# Minisumo_edu.net
KiCad netlist of a schematic drawn in EAGLE
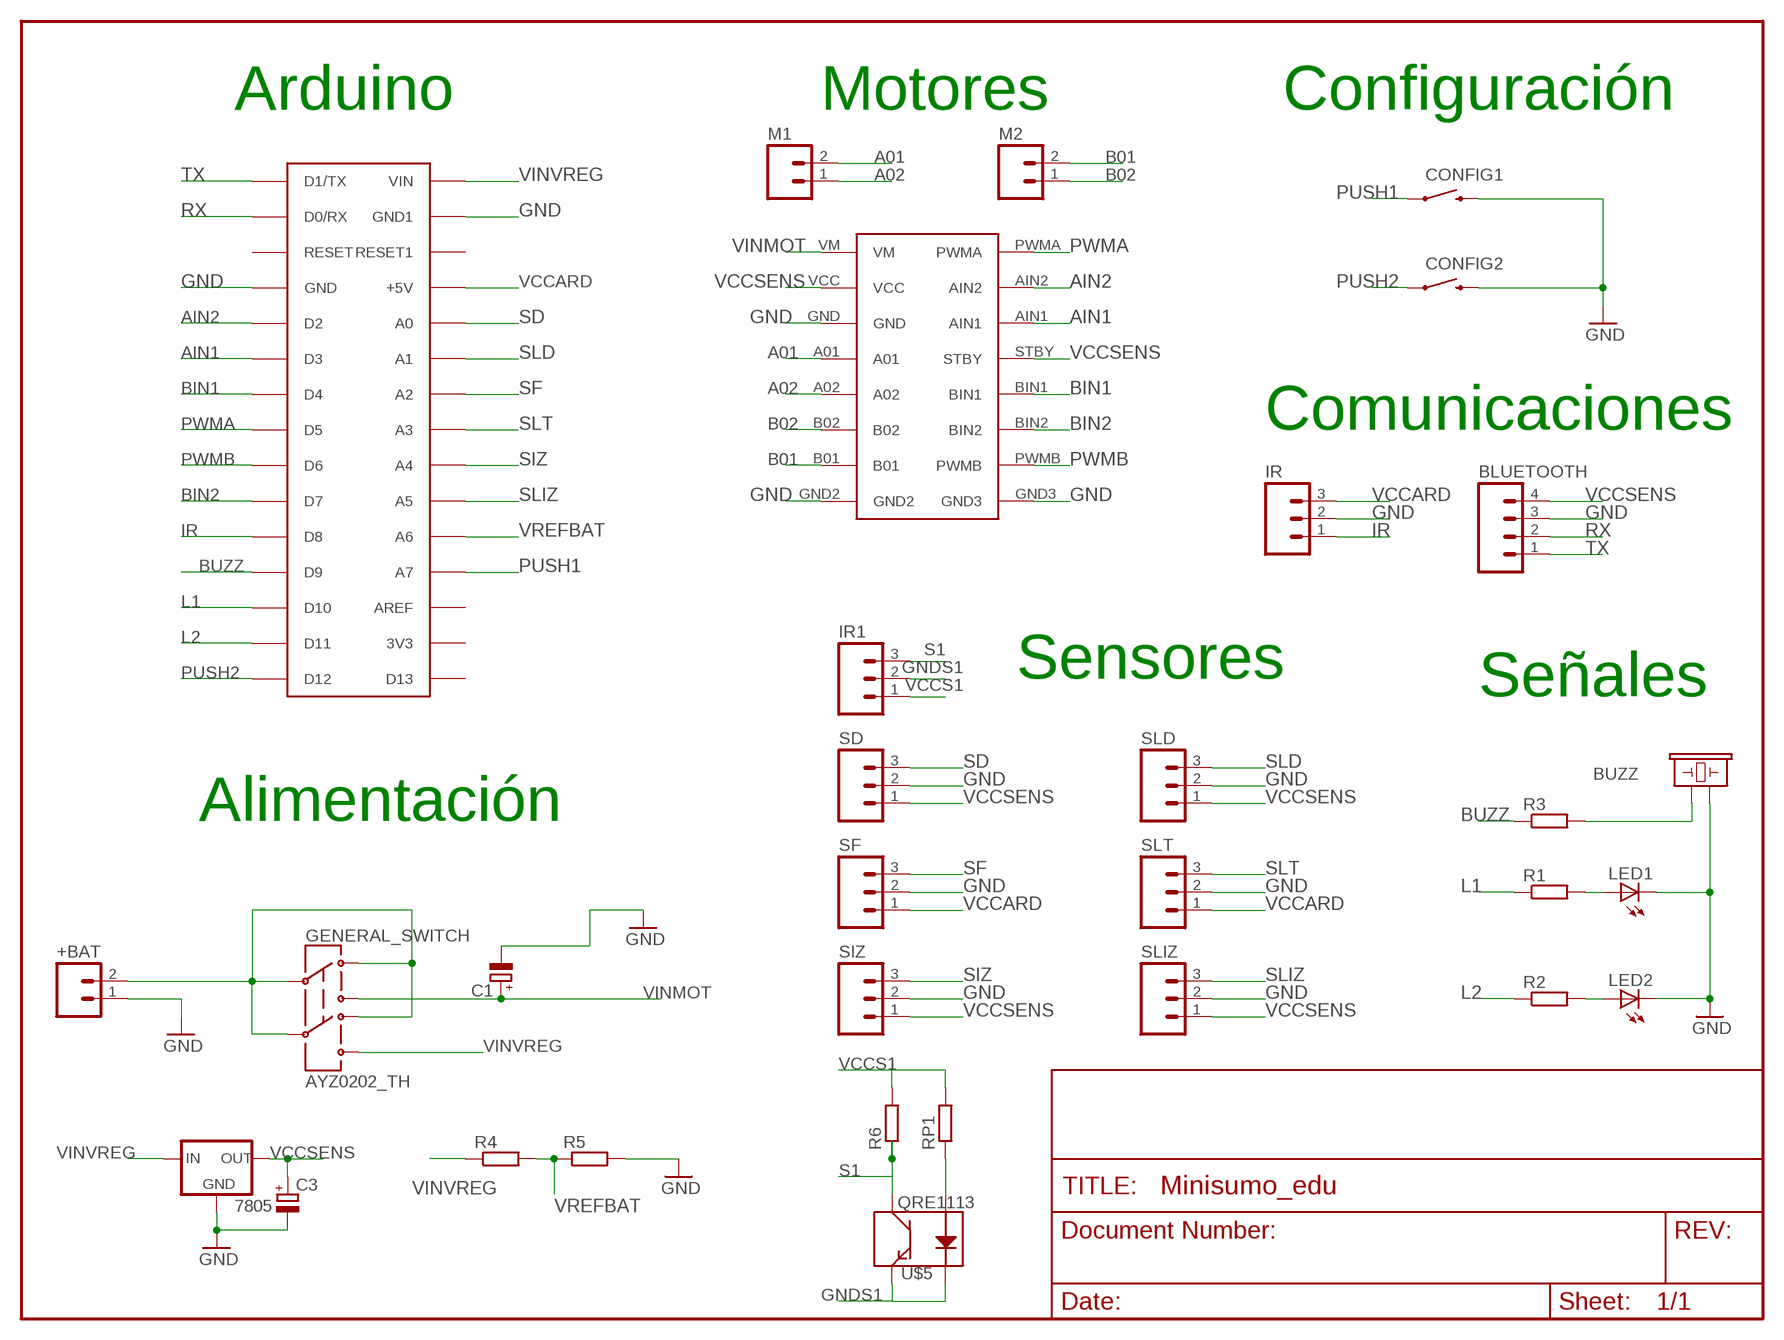
[diagram p0: schematic, sheet 1]

(export (version "E")
  (design (tool "Eeschema 10.0.6"))
  (components
    (comp (ref "+BAT")
      (value "M02LOCK_LONGPADS")
      (footprint "eagle-import:1X02_LOCK_LONGPADS")
      (libsource (lib "eagle-import") (part "M02LOCK_LONGPADS"))
    )
    (comp (ref "7805")
      (value "V_REG_78XXSINK")
      (footprint "eagle-import:TO220-IGO")
      (libsource (lib "eagle-import") (part "V_REG_78XXSINK"))
    )
    (comp (ref "BLUETOOTH")
      (value "M04LONGPADS")
      (footprint "eagle-import:1X04_LONGPADS")
      (libsource (lib "eagle-import") (part "M04LONGPADS"))
    )
    (comp (ref "BUZZ")
      (value "BUZZERPTH")
      (footprint "eagle-import:BUZZER-12MM")
      (libsource (lib "eagle-import") (part "BUZZERPTH"))
    )
    (comp (ref "C1")
      (value "CPOL-EUE2.5-6")
      (footprint "eagle-import:E2,5-6")
      (libsource (lib "eagle-import") (part "CPOL-EUE2.5-6"))
    )
    (comp (ref "C3")
      (value "CPOL-EUE2.5-6")
      (footprint "eagle-import:E2,5-6")
      (libsource (lib "eagle-import") (part "CPOL-EUE2.5-6"))
    )
    (comp (ref "CONFIG1")
      (value "SWITCH-MOMENTARY-2PTH")
      (footprint "eagle-import:TACTILE-PTH")
      (libsource (lib "eagle-import") (part "SWITCH-MOMENTARY-2PTH"))
    )
    (comp (ref "CONFIG2")
      (value "SWITCH-MOMENTARY-2PTH")
      (footprint "eagle-import:TACTILE-PTH")
      (libsource (lib "eagle-import") (part "SWITCH-MOMENTARY-2PTH"))
    )
    (comp (ref "GENERAL_SWITCH")
      (value "AYZ0202_TH")
      (footprint "eagle-import:AYZ0202_TH")
      (libsource (lib "eagle-import") (part "AYZ0202_TH"))
    )
    (comp (ref "IR")
      (value "M03LONGPADS")
      (footprint "eagle-import:1X03_LONGPADS")
      (libsource (lib "eagle-import") (part "M03LONGPADS"))
    )
    (comp (ref "IR1")
      (value "M03LONGPADS")
      (footprint "eagle-import:1X03_LONGPADS")
      (libsource (lib "eagle-import") (part "M03LONGPADS"))
    )
    (comp (ref "LED1")
      (value "LED3MM")
      (footprint "eagle-import:LED3MM")
      (libsource (lib "eagle-import") (part "LED3MM"))
    )
    (comp (ref "LED2")
      (value "LED3MM")
      (footprint "eagle-import:LED3MM")
      (libsource (lib "eagle-import") (part "LED3MM"))
    )
    (comp (ref "M1")
      (value "M02LOCK_LONGPADS")
      (footprint "eagle-import:1X02_LOCK_LONGPADS")
      (libsource (lib "eagle-import") (part "M02LOCK_LONGPADS"))
    )
    (comp (ref "M2")
      (value "M02LOCK_LONGPADS")
      (footprint "eagle-import:1X02_LOCK_LONGPADS")
      (libsource (lib "eagle-import") (part "M02LOCK_LONGPADS"))
    )
    (comp (ref "R1")
      (value "R-EU_0207/7")
      (footprint "eagle-import:0207_7")
      (libsource (lib "eagle-import") (part "R-EU_0207/7"))
    )
    (comp (ref "R2")
      (value "R-EU_0207/7")
      (footprint "eagle-import:0207_7")
      (libsource (lib "eagle-import") (part "R-EU_0207/7"))
    )
    (comp (ref "R3")
      (value "R-EU_0207/7")
      (footprint "eagle-import:0207_7")
      (libsource (lib "eagle-import") (part "R-EU_0207/7"))
    )
    (comp (ref "R4")
      (value "R-EU_0207/7")
      (footprint "eagle-import:0207_7")
      (libsource (lib "eagle-import") (part "R-EU_0207/7"))
    )
    (comp (ref "R5")
      (value "R-EU_0207/7")
      (footprint "eagle-import:0207_7")
      (libsource (lib "eagle-import") (part "R-EU_0207/7"))
    )
    (comp (ref "R6")
      (value "R-EU_M0805")
      (footprint "eagle-import:M0805@1")
      (libsource (lib "eagle-import") (part "resistor_R-EU_M0805"))
    )
    (comp (ref "RP1")
      (value "R-EU_M0805")
      (footprint "eagle-import:M0805")
      (libsource (lib "eagle-import") (part "R-EU_M0805"))
    )
    (comp (ref "SD")
      (value "M03LONGPADS")
      (footprint "eagle-import:1X03_LONGPADS")
      (libsource (lib "eagle-import") (part "M03LONGPADS"))
    )
    (comp (ref "SF")
      (value "M03LONGPADS")
      (footprint "eagle-import:1X03_LONGPADS")
      (libsource (lib "eagle-import") (part "M03LONGPADS"))
    )
    (comp (ref "SIZ")
      (value "M03LONGPADS")
      (footprint "eagle-import:1X03_LONGPADS")
      (libsource (lib "eagle-import") (part "M03LONGPADS"))
    )
    (comp (ref "SLD")
      (value "M03LONGPADS")
      (footprint "eagle-import:1X03_LONGPADS")
      (libsource (lib "eagle-import") (part "M03LONGPADS"))
    )
    (comp (ref "SLIZ")
      (value "M03LONGPADS")
      (footprint "eagle-import:1X03_LONGPADS")
      (libsource (lib "eagle-import") (part "M03LONGPADS"))
    )
    (comp (ref "SLT")
      (value "M03LONGPADS")
      (footprint "eagle-import:1X03_LONGPADS")
      (libsource (lib "eagle-import") (part "M03LONGPADS"))
    )
    (comp (ref "U$1")
      (value "ARDUINONANO")
      (footprint "eagle-import:PDIP-32")
      (libsource (lib "eagle-import") (part "ARDUINONANO"))
    )
    (comp (ref "U$3")
      (value "TB6612FNG_SPARKFUN")
      (footprint "eagle-import:TB6612FNG_SPARKFUN")
      (libsource (lib "eagle-import") (part "TB6612FNG_SPARKFUN"))
    )
    (comp (ref "U$5")
      (value "QRE1113")
      (footprint "eagle-import:QRE1113")
      (libsource (lib "eagle-import") (part "QRE1113"))
    )
  )
  (nets
    (net (code "1") (name "/A01") (class "Default")
      (node (ref "M1") (pin "2") (pinfunction "2_2") (pintype "passive"))
      (node (ref "U$3") (pin "A01") (pinfunction "A01_A01") (pintype "bidirectional"))
    )
    (net (code "2") (name "/A02") (class "Default")
      (node (ref "M1") (pin "1") (pinfunction "1_1") (pintype "passive"))
      (node (ref "U$3") (pin "A02") (pinfunction "A02_A02") (pintype "bidirectional"))
    )
    (net (code "3") (name "/AIN1") (class "Default")
      (node (ref "U$1") (pin "D3") (pinfunction "D3_D3") (pintype "bidirectional"))
      (node (ref "U$3") (pin "AIN1") (pinfunction "AIN1_AIN1") (pintype "bidirectional"))
    )
    (net (code "4") (name "/AIN2") (class "Default")
      (node (ref "U$1") (pin "D2") (pinfunction "D2_D2") (pintype "bidirectional"))
      (node (ref "U$3") (pin "AIN2") (pinfunction "AIN2_AIN2") (pintype "bidirectional"))
    )
    (net (code "5") (name "/B01") (class "Default")
      (node (ref "M2") (pin "2") (pinfunction "2_2") (pintype "passive"))
      (node (ref "U$3") (pin "B01") (pinfunction "B01_B01") (pintype "bidirectional"))
    )
    (net (code "6") (name "/B02") (class "Default")
      (node (ref "M2") (pin "1") (pinfunction "1_1") (pintype "passive"))
      (node (ref "U$3") (pin "B02") (pinfunction "B02_B02") (pintype "bidirectional"))
    )
    (net (code "7") (name "/BIN1") (class "Default")
      (node (ref "U$1") (pin "D4") (pinfunction "D4_D4") (pintype "bidirectional"))
      (node (ref "U$3") (pin "BIN1") (pinfunction "BIN1_BIN1") (pintype "bidirectional"))
    )
    (net (code "8") (name "/BIN2") (class "Default")
      (node (ref "U$1") (pin "D7") (pinfunction "D7_D7") (pintype "bidirectional"))
      (node (ref "U$3") (pin "BIN2") (pinfunction "BIN2_BIN2") (pintype "bidirectional"))
    )
    (net (code "9") (name "/BUZZ") (class "Default")
      (node (ref "R3") (pin "1") (pinfunction "1_1") (pintype "passive"))
      (node (ref "U$1") (pin "D9") (pinfunction "D9_D9") (pintype "bidirectional"))
    )
    (net (code "10") (name "/GNDS1") (class "Default")
      (node (ref "IR1") (pin "2") (pinfunction "2_2") (pintype "passive"))
      (node (ref "U$5") (pin "2") (pinfunction "K_2") (pintype "bidirectional"))
      (node (ref "U$5") (pin "4") (pinfunction "E_4") (pintype "bidirectional"))
    )
    (net (code "11") (name "/IR") (class "Default")
      (node (ref "IR") (pin "1") (pinfunction "1_1") (pintype "passive"))
      (node (ref "U$1") (pin "D8") (pinfunction "D8_D8") (pintype "bidirectional"))
    )
    (net (code "12") (name "/L1") (class "Default")
      (node (ref "R1") (pin "1") (pinfunction "1_1") (pintype "passive"))
      (node (ref "U$1") (pin "D10") (pinfunction "D10_D10") (pintype "bidirectional"))
    )
    (net (code "13") (name "/L2") (class "Default")
      (node (ref "R2") (pin "1") (pinfunction "1_1") (pintype "passive"))
      (node (ref "U$1") (pin "D11") (pinfunction "D11_D11") (pintype "bidirectional"))
    )
    (net (code "14") (name "/PUSH1") (class "Default")
      (node (ref "CONFIG1") (pin "1") (pinfunction "1_1") (pintype "passive"))
      (node (ref "U$1") (pin "A7") (pinfunction "A7_A7") (pintype "bidirectional"))
    )
    (net (code "15") (name "/PUSH2") (class "Default")
      (node (ref "CONFIG2") (pin "1") (pinfunction "1_1") (pintype "passive"))
      (node (ref "U$1") (pin "D12") (pinfunction "D12_D12") (pintype "bidirectional"))
    )
    (net (code "16") (name "/PWMA") (class "Default")
      (node (ref "U$1") (pin "D5") (pinfunction "D5_D5") (pintype "bidirectional"))
      (node (ref "U$3") (pin "PWMA") (pinfunction "PWMA_PWMA") (pintype "bidirectional"))
    )
    (net (code "17") (name "/PWMB") (class "Default")
      (node (ref "U$1") (pin "D6") (pinfunction "D6_D6") (pintype "bidirectional"))
      (node (ref "U$3") (pin "PWMB") (pinfunction "PWMB_PWMB") (pintype "bidirectional"))
    )
    (net (code "18") (name "/RX") (class "Default")
      (node (ref "BLUETOOTH") (pin "2") (pinfunction "2_2") (pintype "passive"))
      (node (ref "U$1") (pin "D0/RX") (pinfunction "D0/RX_D0/RX") (pintype "bidirectional"))
    )
    (net (code "19") (name "/S1") (class "Default")
      (node (ref "IR1") (pin "3") (pinfunction "3_3") (pintype "passive"))
      (node (ref "R6") (pin "1") (pinfunction "1_1") (pintype "passive"))
      (node (ref "U$5") (pin "3") (pinfunction "C_3") (pintype "bidirectional"))
    )
    (net (code "20") (name "/SD") (class "Default")
      (node (ref "SD") (pin "3") (pinfunction "3_3") (pintype "passive"))
      (node (ref "U$1") (pin "A0") (pinfunction "A0_A0") (pintype "bidirectional"))
    )
    (net (code "21") (name "/SF") (class "Default")
      (node (ref "SF") (pin "3") (pinfunction "3_3") (pintype "passive"))
      (node (ref "U$1") (pin "A2") (pinfunction "A2_A2") (pintype "bidirectional"))
    )
    (net (code "22") (name "/SIZ") (class "Default")
      (node (ref "SIZ") (pin "3") (pinfunction "3_3") (pintype "passive"))
      (node (ref "U$1") (pin "A4") (pinfunction "A4_A4") (pintype "bidirectional"))
    )
    (net (code "23") (name "/SLD") (class "Default")
      (node (ref "SLD") (pin "3") (pinfunction "3_3") (pintype "passive"))
      (node (ref "U$1") (pin "A1") (pinfunction "A1_A1") (pintype "bidirectional"))
    )
    (net (code "24") (name "/SLIZ") (class "Default")
      (node (ref "SLIZ") (pin "3") (pinfunction "3_3") (pintype "passive"))
      (node (ref "U$1") (pin "A5") (pinfunction "A5_A5") (pintype "bidirectional"))
    )
    (net (code "25") (name "/SLT") (class "Default")
      (node (ref "SLT") (pin "3") (pinfunction "3_3") (pintype "passive"))
      (node (ref "U$1") (pin "A3") (pinfunction "A3_A3") (pintype "bidirectional"))
    )
    (net (code "26") (name "/TX") (class "Default")
      (node (ref "BLUETOOTH") (pin "1") (pinfunction "1_1") (pintype "passive"))
      (node (ref "U$1") (pin "D1/TX") (pinfunction "D1/TX_D1/TX") (pintype "bidirectional"))
    )
    (net (code "27") (name "/VCCARD") (class "Default")
      (node (ref "IR") (pin "3") (pinfunction "3_3") (pintype "passive"))
      (node (ref "SF") (pin "1") (pinfunction "1_1") (pintype "passive"))
      (node (ref "SLT") (pin "1") (pinfunction "1_1") (pintype "passive"))
      (node (ref "U$1") (pin "+5V") (pinfunction "+5V_+5V") (pintype "bidirectional"))
    )
    (net (code "28") (name "/VCCS1") (class "Default")
      (node (ref "IR1") (pin "1") (pinfunction "1_1") (pintype "passive"))
      (node (ref "R6") (pin "2") (pinfunction "2_2") (pintype "passive"))
      (node (ref "RP1") (pin "2") (pinfunction "2_2") (pintype "passive"))
    )
    (net (code "29") (name "/VCCSENS") (class "Default")
      (node (ref "7805") (pin "OUT") (pinfunction "OUT_OUT") (pintype "output"))
      (node (ref "BLUETOOTH") (pin "4") (pinfunction "4_4") (pintype "passive"))
      (node (ref "C3") (pin "+") (pinfunction "+_+") (pintype "passive"))
      (node (ref "SD") (pin "1") (pinfunction "1_1") (pintype "passive"))
      (node (ref "SIZ") (pin "1") (pinfunction "1_1") (pintype "passive"))
      (node (ref "SLD") (pin "1") (pinfunction "1_1") (pintype "passive"))
      (node (ref "SLIZ") (pin "1") (pinfunction "1_1") (pintype "passive"))
      (node (ref "U$3") (pin "STBY") (pinfunction "STBY_STBY") (pintype "bidirectional"))
      (node (ref "U$3") (pin "VCC") (pinfunction "VCC_VCC") (pintype "bidirectional"))
    )
    (net (code "30") (name "/VINMOT") (class "Default")
      (node (ref "C1") (pin "+") (pinfunction "+_+") (pintype "passive"))
      (node (ref "GENERAL_SWITCH") (pin "B1") (pinfunction "B1_B1") (pintype "bidirectional"))
      (node (ref "U$3") (pin "VM") (pinfunction "VM_VM") (pintype "bidirectional"))
    )
    (net (code "31") (name "/VINVREG") (class "Default")
      (node (ref "7805") (pin "IN") (pinfunction "IN_IN") (pintype "input"))
      (node (ref "GENERAL_SWITCH") (pin "B2") (pinfunction "B2_B2") (pintype "bidirectional"))
      (node (ref "R4") (pin "1") (pinfunction "1_1") (pintype "passive"))
      (node (ref "U$1") (pin "VIN") (pinfunction "VIN_VIN") (pintype "bidirectional"))
    )
    (net (code "32") (name "/VREFBAT") (class "Default")
      (node (ref "R4") (pin "2") (pinfunction "2_2") (pintype "passive"))
      (node (ref "R5") (pin "1") (pinfunction "1_1") (pintype "passive"))
      (node (ref "U$1") (pin "A6") (pinfunction "A6_A6") (pintype "bidirectional"))
    )
    (net (code "33") (name "GND") (class "Default")
      (node (ref "+BAT") (pin "1") (pinfunction "1_1") (pintype "passive"))
      (node (ref "7805") (pin "GND") (pinfunction "GND_GND") (pintype "input"))
      (node (ref "BLUETOOTH") (pin "3") (pinfunction "3_3") (pintype "passive"))
      (node (ref "BUZZ") (pin "-") (pinfunction "2_-") (pintype "passive"))
      (node (ref "C1") (pin "-") (pinfunction "-_-") (pintype "passive"))
      (node (ref "C3") (pin "-") (pinfunction "-_-") (pintype "passive"))
      (node (ref "CONFIG1") (pin "3") (pinfunction "2_3") (pintype "passive"))
      (node (ref "CONFIG2") (pin "3") (pinfunction "2_3") (pintype "passive"))
      (node (ref "IR") (pin "2") (pinfunction "2_2") (pintype "passive"))
      (node (ref "LED1") (pin "K") (pinfunction "C_K") (pintype "passive"))
      (node (ref "LED2") (pin "K") (pinfunction "C_K") (pintype "passive"))
      (node (ref "R5") (pin "2") (pinfunction "2_2") (pintype "passive"))
      (node (ref "SD") (pin "2") (pinfunction "2_2") (pintype "passive"))
      (node (ref "SF") (pin "2") (pinfunction "2_2") (pintype "passive"))
      (node (ref "SIZ") (pin "2") (pinfunction "2_2") (pintype "passive"))
      (node (ref "SLD") (pin "2") (pinfunction "2_2") (pintype "passive"))
      (node (ref "SLIZ") (pin "2") (pinfunction "2_2") (pintype "passive"))
      (node (ref "SLT") (pin "2") (pinfunction "2_2") (pintype "passive"))
      (node (ref "U$1") (pin "GND") (pinfunction "GND_GND") (pintype "bidirectional"))
      (node (ref "U$1") (pin "GND1") (pinfunction "GND1_GND1") (pintype "bidirectional"))
      (node (ref "U$3") (pin "GND") (pinfunction "GND_GND") (pintype "bidirectional"))
      (node (ref "U$3") (pin "GND2") (pinfunction "GND2_GND2") (pintype "bidirectional"))
      (node (ref "U$3") (pin "GND3") (pinfunction "GND3_GND3") (pintype "bidirectional"))
    )
    (net (code "34") (name "Net-(+BAT-Pad2)") (class "Default")
      (node (ref "+BAT") (pin "2") (pinfunction "2_2") (pintype "passive"))
      (node (ref "GENERAL_SWITCH") (pin "C1") (pinfunction "C1_C1") (pintype "bidirectional"))
      (node (ref "GENERAL_SWITCH") (pin "C2") (pinfunction "C2_C2") (pintype "bidirectional"))
      (node (ref "GENERAL_SWITCH") (pin "D1") (pinfunction "D1_D1") (pintype "bidirectional"))
      (node (ref "GENERAL_SWITCH") (pin "D2") (pinfunction "D2_D2") (pintype "bidirectional"))
    )
    (net (code "35") (name "Net-(BUZZ-1)") (class "Default")
      (node (ref "BUZZ") (pin "+") (pinfunction "1_+") (pintype "passive"))
      (node (ref "R3") (pin "2") (pinfunction "2_2") (pintype "passive"))
    )
    (net (code "36") (name "Net-(LED1-PadA)") (class "Default")
      (node (ref "LED1") (pin "A") (pinfunction "A_A") (pintype "passive"))
      (node (ref "R1") (pin "2") (pinfunction "2_2") (pintype "passive"))
    )
    (net (code "37") (name "Net-(LED2-PadA)") (class "Default")
      (node (ref "LED2") (pin "A") (pinfunction "A_A") (pintype "passive"))
      (node (ref "R2") (pin "2") (pinfunction "2_2") (pintype "passive"))
    )
    (net (code "38") (name "Net-(U$5-A)") (class "Default")
      (node (ref "RP1") (pin "1") (pinfunction "1_1") (pintype "passive"))
      (node (ref "U$5") (pin "1") (pinfunction "A_1") (pintype "bidirectional"))
    )
    (net (code "39") (name "unconnected-(U$1-Pad3V3)") (class "Default")
      (node (ref "U$1") (pin "3V3") (pinfunction "3V3_3V3") (pintype "bidirectional"))
    )
    (net (code "40") (name "unconnected-(U$1-PadAREF)") (class "Default")
      (node (ref "U$1") (pin "AREF") (pinfunction "AREF_AREF") (pintype "bidirectional"))
    )
    (net (code "41") (name "unconnected-(U$1-PadD13)") (class "Default")
      (node (ref "U$1") (pin "D13") (pinfunction "D13_D13") (pintype "bidirectional"))
    )
    (net (code "42") (name "unconnected-(U$1-PadRESET)") (class "Default")
      (node (ref "U$1") (pin "RESET") (pinfunction "RESET_RESET") (pintype "bidirectional"))
    )
    (net (code "43") (name "unconnected-(U$1-PadRESET1)") (class "Default")
      (node (ref "U$1") (pin "RESET1") (pinfunction "RESET1_RESET1") (pintype "bidirectional"))
    )
  )
)
